# Relay_Board_V3.net
KiCad netlist of a schematic drawn in EAGLE
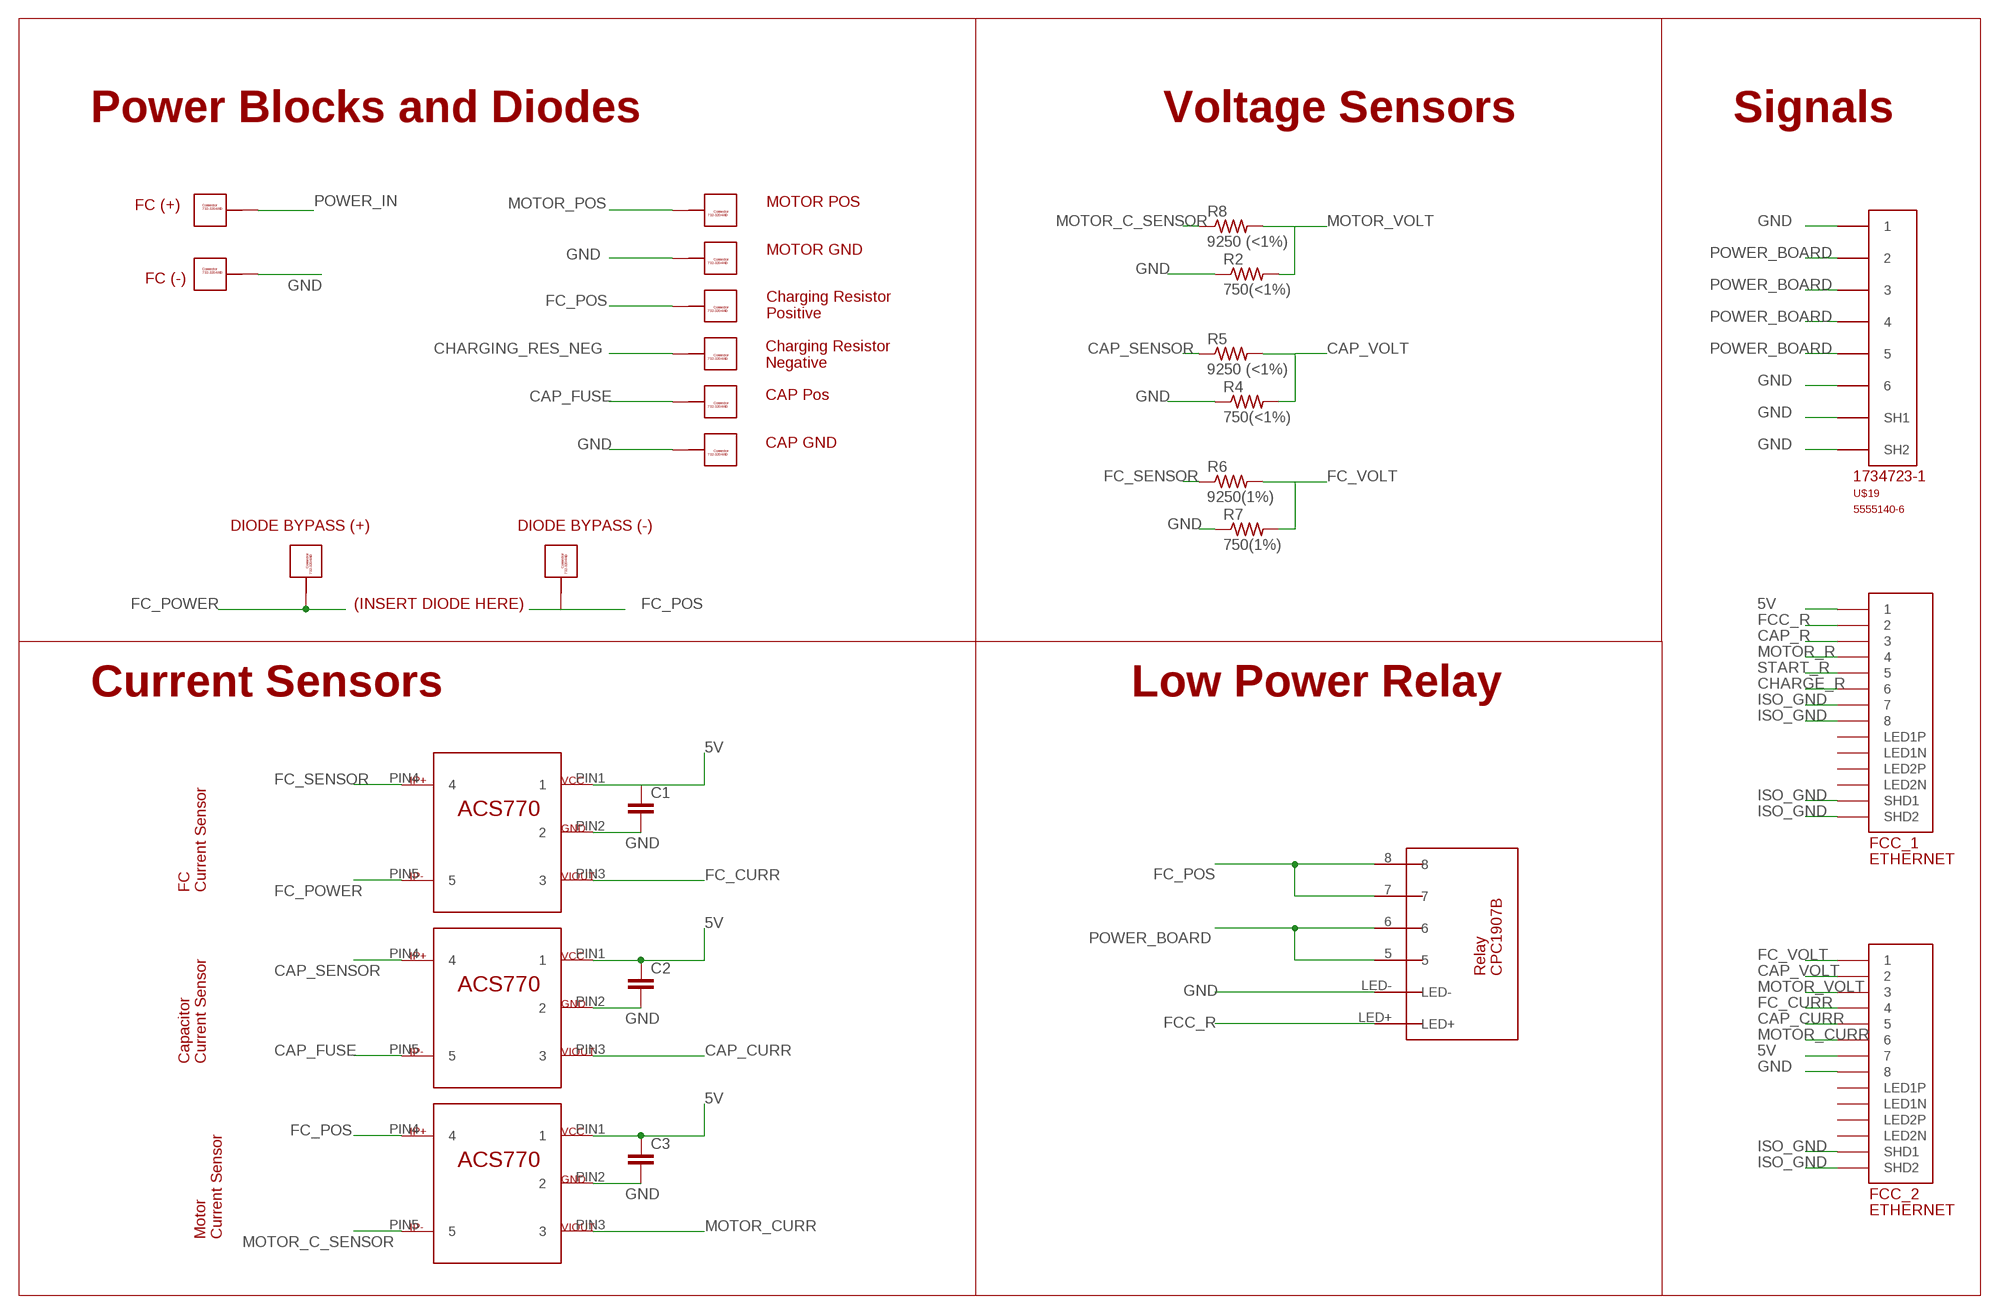
[diagram p0: schematic, sheet 1]
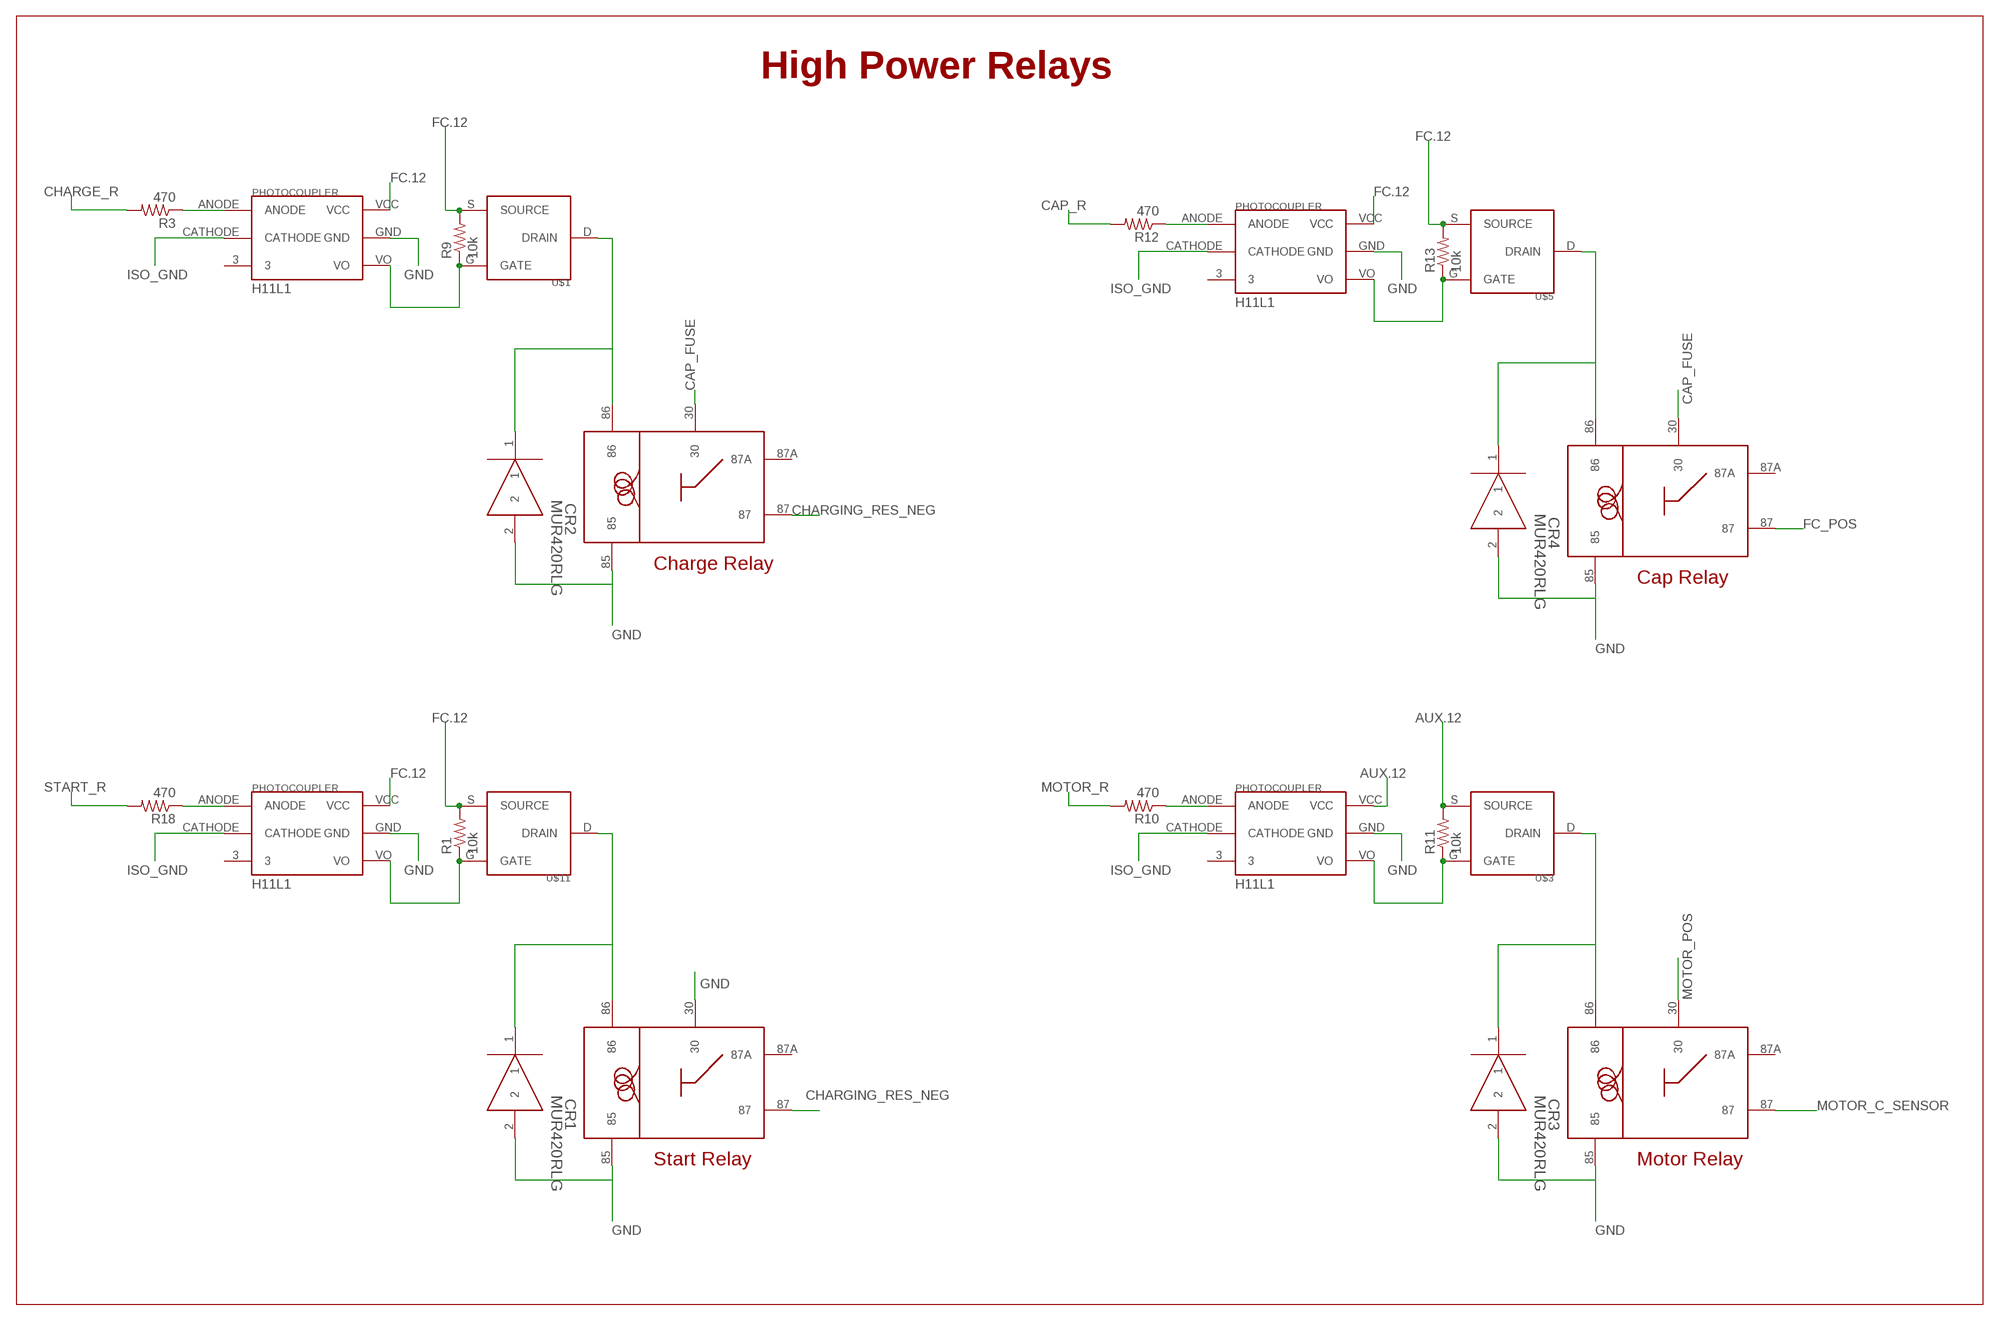
[diagram p1: schematic, sheet 2]

(export (version "E")
  (design (tool "Eeschema 10.0.6"))
  (components
    (comp (ref "C1")
      (value "CAP0603-CAP")
      (footprint "eagle-import:0603-CAP")
      (libsource (lib "eagle-import") (part "CAP0603-CAP"))
    )
    (comp (ref "C2")
      (value "CAP0603-CAP")
      (footprint "eagle-import:0603-CAP")
      (libsource (lib "eagle-import") (part "CAP0603-CAP"))
    )
    (comp (ref "C3")
      (value "CAP0603-CAP")
      (footprint "eagle-import:0603-CAP")
      (libsource (lib "eagle-import") (part "CAP0603-CAP"))
    )
    (comp (ref "CAP.GND")
      (value "732-3204-ND_CONNECTOR")
      (footprint "eagle-import:732-3204-ND")
      (libsource (lib "eagle-import") (part "732-3204-ND_CONNECTOR"))
    )
    (comp (ref "CAP.GND1")
      (value "732-3204-ND_CONNECTOR")
      (footprint "eagle-import:732-3204-ND")
      (libsource (lib "eagle-import") (part "732-3204-ND_CONNECTOR"))
    )
    (comp (ref "CAP.POS1")
      (value "732-3204-ND_CONNECTOR")
      (footprint "eagle-import:732-3204-ND")
      (libsource (lib "eagle-import") (part "732-3204-ND_CONNECTOR"))
    )
    (comp (ref "CAP.POS2")
      (value "732-3204-ND_CONNECTOR")
      (footprint "eagle-import:732-3204-ND")
      (libsource (lib "eagle-import") (part "732-3204-ND_CONNECTOR"))
    )
    (comp (ref "FC.GND")
      (value "732-3204-ND_CONNECTOR")
      (footprint "eagle-import:732-3204-ND")
      (libsource (lib "eagle-import") (part "732-3204-ND_CONNECTOR"))
    )
    (comp (ref "FC.POS")
      (value "732-3204-ND_CONNECTOR")
      (footprint "eagle-import:732-3204-ND")
      (libsource (lib "eagle-import") (part "732-3204-ND_CONNECTOR"))
    )
    (comp (ref "FCC_1")
      (value "ETHERNET")
      (footprint "eagle-import:A122645-ND")
      (libsource (lib "eagle-import") (part "ETHERNET"))
    )
    (comp (ref "FCC_2")
      (value "ETHERNET")
      (footprint "eagle-import:A122645-ND")
      (libsource (lib "eagle-import") (part "ETHERNET"))
    )
    (comp (ref "MOTOR.GROUND")
      (value "732-3204-ND_CONNECTOR")
      (footprint "eagle-import:732-3204-ND")
      (libsource (lib "eagle-import") (part "732-3204-ND_CONNECTOR"))
    )
    (comp (ref "MOTOR.POSITIVE")
      (value "732-3204-ND_CONNECTOR")
      (footprint "eagle-import:732-3204-ND")
      (libsource (lib "eagle-import") (part "732-3204-ND_CONNECTOR"))
    )
    (comp (ref "R2")
      (value "750(<1%)")
      (footprint "eagle-import:R0805")
      (libsource (lib "eagle-import") (part "R-US_R0805"))
    )
    (comp (ref "R4")
      (value "750(<1%)")
      (footprint "eagle-import:R0805")
      (libsource (lib "eagle-import") (part "R-US_R0805"))
    )
    (comp (ref "R5")
      (value "9250 (<1%)")
      (footprint "eagle-import:R0805")
      (libsource (lib "eagle-import") (part "R-US_R0805"))
    )
    (comp (ref "R6")
      (value "9250(1%)")
      (footprint "eagle-import:R0805")
      (libsource (lib "eagle-import") (part "R-US_R0805"))
    )
    (comp (ref "R7")
      (value "750(1%)")
      (footprint "eagle-import:R0805")
      (libsource (lib "eagle-import") (part "R-US_R0805"))
    )
    (comp (ref "R8")
      (value "9250 (<1%)")
      (footprint "eagle-import:R0805")
      (libsource (lib "eagle-import") (part "R-US_R0805"))
    )
    (comp (ref "RES.NEG")
      (value "732-3204-ND_CONNECTOR")
      (footprint "eagle-import:732-3204-ND")
      (libsource (lib "eagle-import") (part "732-3204-ND_CONNECTOR"))
    )
    (comp (ref "RES.POS")
      (value "732-3204-ND_CONNECTOR")
      (footprint "eagle-import:732-3204-ND")
      (libsource (lib "eagle-import") (part "732-3204-ND_CONNECTOR"))
    )
    (comp (ref "U$7")
      (value "ACS770LCB_CURRENTSENSOR")
      (footprint "eagle-import:ACS770LCB_CURRENTSENSOR")
      (libsource (lib "eagle-import") (part "ACS770LCB_CURRENTSENSOR"))
    )
    (comp (ref "U$8")
      (value "ACS770LCB_CURRENTSENSOR")
      (footprint "eagle-import:ACS770LCB_CURRENTSENSOR")
      (libsource (lib "eagle-import") (part "ACS770LCB_CURRENTSENSOR"))
    )
    (comp (ref "U$9")
      (value "ACS770LCB_CURRENTSENSOR")
      (footprint "eagle-import:ACS770LCB_CURRENTSENSOR")
      (libsource (lib "eagle-import") (part "ACS770LCB_CURRENTSENSOR"))
    )
    (comp (ref "U$19")
      (value "5555140-6")
      (footprint "eagle-import:1734723-1_RJ11")
      (libsource (lib "eagle-import") (part "5555140-6"))
    )
    (comp (ref "U$22")
      (value "RELAY-CPC1907B")
      (footprint "eagle-import:RELAY-CPC1907B")
      (libsource (lib "eagle-import") (part "RELAY-CPC1907B"))
    )
    (comp (ref "CR1")
      (value "MUR420RLG")
      (footprint "eagle-import:DO-201AD")
      (libsource (lib "eagle-import") (part "MUR420RLG"))
    )
    (comp (ref "CR2")
      (value "MUR420RLG")
      (footprint "eagle-import:DO-201AD")
      (libsource (lib "eagle-import") (part "MUR420RLG"))
    )
    (comp (ref "CR3")
      (value "MUR420RLG")
      (footprint "eagle-import:DO-201AD")
      (libsource (lib "eagle-import") (part "MUR420RLG"))
    )
    (comp (ref "CR4")
      (value "MUR420RLG")
      (footprint "eagle-import:DO-201AD")
      (libsource (lib "eagle-import") (part "MUR420RLG"))
    )
    (comp (ref "R1")
      (value "10k")
      (footprint "eagle-import:0603-RES")
      (libsource (lib "eagle-import") (part "RESISTOR0603-RES"))
    )
    (comp (ref "R3")
      (value "470")
      (footprint "eagle-import:0603-RES")
      (libsource (lib "eagle-import") (part "RESISTOR0603-RES"))
    )
    (comp (ref "R9")
      (value "10k")
      (footprint "eagle-import:0603-RES")
      (libsource (lib "eagle-import") (part "RESISTOR0603-RES"))
    )
    (comp (ref "R10")
      (value "470")
      (footprint "eagle-import:0603-RES")
      (libsource (lib "eagle-import") (part "RESISTOR0603-RES"))
    )
    (comp (ref "R11")
      (value "10k")
      (footprint "eagle-import:0603-RES")
      (libsource (lib "eagle-import") (part "RESISTOR0603-RES"))
    )
    (comp (ref "R12")
      (value "470")
      (footprint "eagle-import:0603-RES")
      (libsource (lib "eagle-import") (part "RESISTOR0603-RES"))
    )
    (comp (ref "R13")
      (value "10k")
      (footprint "eagle-import:0603-RES")
      (libsource (lib "eagle-import") (part "RESISTOR0603-RES"))
    )
    (comp (ref "R18")
      (value "470")
      (footprint "eagle-import:0603-RES")
      (libsource (lib "eagle-import") (part "RESISTOR0603-RES"))
    )
    (comp (ref "START.RELAY1")
      (value "VCF4-1000")
      (footprint "eagle-import:VCF4-1000")
      (libsource (lib "eagle-import") (part "VCF4-1000"))
    )
    (comp (ref "START.RELAY2")
      (value "VCF4-1000")
      (footprint "eagle-import:VCF4-1000")
      (libsource (lib "eagle-import") (part "VCF4-1000"))
    )
    (comp (ref "START.RELAY3")
      (value "VCF4-1000")
      (footprint "eagle-import:VCF4-1000")
      (libsource (lib "eagle-import") (part "VCF4-1000"))
    )
    (comp (ref "START.RELAY4")
      (value "VCF4-1000")
      (footprint "eagle-import:VCF4-1000")
      (libsource (lib "eagle-import") (part "VCF4-1000"))
    )
    (comp (ref "U$1")
      (value "DMP3056L-7DMP3056L-7")
      (footprint "eagle-import:DMP3056L-7")
      (libsource (lib "eagle-import") (part "DMP3056L-7DMP3056L-7"))
    )
    (comp (ref "U$2")
      (value "H11L1H11L1")
      (footprint "eagle-import:H11L1")
      (libsource (lib "eagle-import") (part "H11L1H11L1"))
    )
    (comp (ref "U$3")
      (value "DMP3056L-7DMP3056L-7")
      (footprint "eagle-import:DMP3056L-7")
      (libsource (lib "eagle-import") (part "DMP3056L-7DMP3056L-7"))
    )
    (comp (ref "U$4")
      (value "H11L1H11L1")
      (footprint "eagle-import:H11L1")
      (libsource (lib "eagle-import") (part "H11L1H11L1"))
    )
    (comp (ref "U$5")
      (value "DMP3056L-7DMP3056L-7")
      (footprint "eagle-import:DMP3056L-7")
      (libsource (lib "eagle-import") (part "DMP3056L-7DMP3056L-7"))
    )
    (comp (ref "U$6")
      (value "H11L1H11L1")
      (footprint "eagle-import:H11L1")
      (libsource (lib "eagle-import") (part "H11L1H11L1"))
    )
    (comp (ref "U$11")
      (value "DMP3056L-7DMP3056L-7")
      (footprint "eagle-import:DMP3056L-7")
      (libsource (lib "eagle-import") (part "DMP3056L-7DMP3056L-7"))
    )
    (comp (ref "U$12")
      (value "H11L1H11L1")
      (footprint "eagle-import:H11L1")
      (libsource (lib "eagle-import") (part "H11L1H11L1"))
    )
  )
  (nets
    (net (code "1") (name "5V") (class "Default")
      (node (ref "C1") (pin "1") (pinfunction "1_1") (pintype "passive"))
      (node (ref "C2") (pin "1") (pinfunction "1_1") (pintype "passive"))
      (node (ref "C3") (pin "1") (pinfunction "1_1") (pintype "passive"))
      (node (ref "FCC_1") (pin "P$1") (pinfunction "1_P$1") (pintype "bidirectional"))
      (node (ref "FCC_2") (pin "P$7") (pinfunction "7_P$7") (pintype "bidirectional"))
      (node (ref "U$7") (pin "PIN1") (pinfunction "1_PIN1") (pintype "bidirectional"))
      (node (ref "U$8") (pin "PIN1") (pinfunction "1_PIN1") (pintype "bidirectional"))
      (node (ref "U$9") (pin "PIN1") (pinfunction "1_PIN1") (pintype "bidirectional"))
    )
    (net (code "2") (name "AUX.12") (class "Default")
      (node (ref "R11") (pin "2") (pinfunction "2_2") (pintype "passive"))
      (node (ref "U$3") (pin "S") (pinfunction "SOURCE_S") (pintype "bidirectional"))
      (node (ref "U$4") (pin "VCC") (pinfunction "VCC_VCC") (pintype "bidirectional"))
    )
    (net (code "3") (name "CAP_CURR") (class "Default")
      (node (ref "FCC_2") (pin "P$5") (pinfunction "5_P$5") (pintype "bidirectional"))
      (node (ref "U$8") (pin "PIN3") (pinfunction "3_PIN3") (pintype "bidirectional"))
    )
    (net (code "4") (name "CAP_FUSE") (class "Default")
      (node (ref "CAP.GND1") (pin "P$1") (pinfunction "P$1_P$1") (pintype "bidirectional"))
      (node (ref "CAP.GND1") (pin "P$10") (pinfunction "P$1_P$10") (pintype "bidirectional"))
      (node (ref "CAP.GND1") (pin "P$2") (pinfunction "P$1_P$2") (pintype "bidirectional"))
      (node (ref "CAP.GND1") (pin "P$3") (pinfunction "P$1_P$3") (pintype "bidirectional"))
      (node (ref "CAP.GND1") (pin "P$4") (pinfunction "P$1_P$4") (pintype "bidirectional"))
      (node (ref "CAP.GND1") (pin "P$5") (pinfunction "P$1_P$5") (pintype "bidirectional"))
      (node (ref "CAP.GND1") (pin "P$6") (pinfunction "P$1_P$6") (pintype "bidirectional"))
      (node (ref "CAP.GND1") (pin "P$7") (pinfunction "P$1_P$7") (pintype "bidirectional"))
      (node (ref "CAP.GND1") (pin "P$8") (pinfunction "P$1_P$8") (pintype "bidirectional"))
      (node (ref "CAP.GND1") (pin "P$9") (pinfunction "P$1_P$9") (pintype "bidirectional"))
      (node (ref "START.RELAY2") (pin "30") (pinfunction "30_30") (pintype "bidirectional"))
      (node (ref "START.RELAY4") (pin "30") (pinfunction "30_30") (pintype "bidirectional"))
      (node (ref "U$8") (pin "PIN5") (pinfunction "5_PIN5") (pintype "bidirectional"))
    )
    (net (code "5") (name "CAP_R") (class "Default")
      (node (ref "FCC_1") (pin "P$3") (pinfunction "3_P$3") (pintype "bidirectional"))
      (node (ref "R12") (pin "2") (pinfunction "2_2") (pintype "passive"))
    )
    (net (code "6") (name "CAP_SENSOR") (class "Default")
      (node (ref "R5") (pin "1") (pinfunction "1_1") (pintype "passive"))
      (node (ref "U$8") (pin "PIN4") (pinfunction "4_PIN4") (pintype "bidirectional"))
    )
    (net (code "7") (name "CAP_VOLT") (class "Default")
      (node (ref "FCC_2") (pin "P$2") (pinfunction "2_P$2") (pintype "bidirectional"))
      (node (ref "R4") (pin "2") (pinfunction "2_2") (pintype "passive"))
      (node (ref "R5") (pin "2") (pinfunction "2_2") (pintype "passive"))
    )
    (net (code "8") (name "CHARGE_R") (class "Default")
      (node (ref "FCC_1") (pin "P$6") (pinfunction "6_P$6") (pintype "bidirectional"))
      (node (ref "R3") (pin "2") (pinfunction "2_2") (pintype "passive"))
    )
    (net (code "9") (name "CHARGING_RES_NEG") (class "Default")
      (node (ref "RES.NEG") (pin "P$1") (pinfunction "P$1_P$1") (pintype "bidirectional"))
      (node (ref "RES.NEG") (pin "P$10") (pinfunction "P$1_P$10") (pintype "bidirectional"))
      (node (ref "RES.NEG") (pin "P$2") (pinfunction "P$1_P$2") (pintype "bidirectional"))
      (node (ref "RES.NEG") (pin "P$3") (pinfunction "P$1_P$3") (pintype "bidirectional"))
      (node (ref "RES.NEG") (pin "P$4") (pinfunction "P$1_P$4") (pintype "bidirectional"))
      (node (ref "RES.NEG") (pin "P$5") (pinfunction "P$1_P$5") (pintype "bidirectional"))
      (node (ref "RES.NEG") (pin "P$6") (pinfunction "P$1_P$6") (pintype "bidirectional"))
      (node (ref "RES.NEG") (pin "P$7") (pinfunction "P$1_P$7") (pintype "bidirectional"))
      (node (ref "RES.NEG") (pin "P$8") (pinfunction "P$1_P$8") (pintype "bidirectional"))
      (node (ref "RES.NEG") (pin "P$9") (pinfunction "P$1_P$9") (pintype "bidirectional"))
      (node (ref "START.RELAY1") (pin "87") (pinfunction "87_87") (pintype "bidirectional"))
      (node (ref "START.RELAY2") (pin "87") (pinfunction "87_87") (pintype "bidirectional"))
    )
    (net (code "10") (name "FC.12") (class "Default")
      (node (ref "R1") (pin "2") (pinfunction "2_2") (pintype "passive"))
      (node (ref "R13") (pin "2") (pinfunction "2_2") (pintype "passive"))
      (node (ref "R9") (pin "2") (pinfunction "2_2") (pintype "passive"))
      (node (ref "U$1") (pin "S") (pinfunction "SOURCE_S") (pintype "bidirectional"))
      (node (ref "U$11") (pin "S") (pinfunction "SOURCE_S") (pintype "bidirectional"))
      (node (ref "U$12") (pin "VCC") (pinfunction "VCC_VCC") (pintype "bidirectional"))
      (node (ref "U$2") (pin "VCC") (pinfunction "VCC_VCC") (pintype "bidirectional"))
      (node (ref "U$5") (pin "S") (pinfunction "SOURCE_S") (pintype "bidirectional"))
      (node (ref "U$6") (pin "VCC") (pinfunction "VCC_VCC") (pintype "bidirectional"))
    )
    (net (code "11") (name "FCC_R") (class "Default")
      (node (ref "FCC_1") (pin "P$2") (pinfunction "2_P$2") (pintype "bidirectional"))
      (node (ref "U$22") (pin "LED+") (pinfunction "LED+_LED+") (pintype "bidirectional"))
    )
    (net (code "12") (name "FC_CURR") (class "Default")
      (node (ref "FCC_2") (pin "P$4") (pinfunction "4_P$4") (pintype "bidirectional"))
      (node (ref "U$7") (pin "PIN3") (pinfunction "3_PIN3") (pintype "bidirectional"))
    )
    (net (code "13") (name "FC_POS") (class "Default")
      (node (ref "CAP.POS2") (pin "P$1") (pinfunction "P$1_P$1") (pintype "bidirectional"))
      (node (ref "CAP.POS2") (pin "P$10") (pinfunction "P$1_P$10") (pintype "bidirectional"))
      (node (ref "CAP.POS2") (pin "P$2") (pinfunction "P$1_P$2") (pintype "bidirectional"))
      (node (ref "CAP.POS2") (pin "P$3") (pinfunction "P$1_P$3") (pintype "bidirectional"))
      (node (ref "CAP.POS2") (pin "P$4") (pinfunction "P$1_P$4") (pintype "bidirectional"))
      (node (ref "CAP.POS2") (pin "P$5") (pinfunction "P$1_P$5") (pintype "bidirectional"))
      (node (ref "CAP.POS2") (pin "P$6") (pinfunction "P$1_P$6") (pintype "bidirectional"))
      (node (ref "CAP.POS2") (pin "P$7") (pinfunction "P$1_P$7") (pintype "bidirectional"))
      (node (ref "CAP.POS2") (pin "P$8") (pinfunction "P$1_P$8") (pintype "bidirectional"))
      (node (ref "CAP.POS2") (pin "P$9") (pinfunction "P$1_P$9") (pintype "bidirectional"))
      (node (ref "RES.POS") (pin "P$1") (pinfunction "P$1_P$1") (pintype "bidirectional"))
      (node (ref "RES.POS") (pin "P$10") (pinfunction "P$1_P$10") (pintype "bidirectional"))
      (node (ref "RES.POS") (pin "P$2") (pinfunction "P$1_P$2") (pintype "bidirectional"))
      (node (ref "RES.POS") (pin "P$3") (pinfunction "P$1_P$3") (pintype "bidirectional"))
      (node (ref "RES.POS") (pin "P$4") (pinfunction "P$1_P$4") (pintype "bidirectional"))
      (node (ref "RES.POS") (pin "P$5") (pinfunction "P$1_P$5") (pintype "bidirectional"))
      (node (ref "RES.POS") (pin "P$6") (pinfunction "P$1_P$6") (pintype "bidirectional"))
      (node (ref "RES.POS") (pin "P$7") (pinfunction "P$1_P$7") (pintype "bidirectional"))
      (node (ref "RES.POS") (pin "P$8") (pinfunction "P$1_P$8") (pintype "bidirectional"))
      (node (ref "RES.POS") (pin "P$9") (pinfunction "P$1_P$9") (pintype "bidirectional"))
      (node (ref "START.RELAY4") (pin "87") (pinfunction "87_87") (pintype "bidirectional"))
      (node (ref "U$22") (pin "7") (pinfunction "7_7") (pintype "bidirectional"))
      (node (ref "U$22") (pin "8") (pinfunction "8_8") (pintype "bidirectional"))
      (node (ref "U$9") (pin "PIN4") (pinfunction "4_PIN4") (pintype "bidirectional"))
    )
    (net (code "14") (name "FC_POWER") (class "Default")
      (node (ref "CAP.POS1") (pin "P$1") (pinfunction "P$1_P$1") (pintype "bidirectional"))
      (node (ref "CAP.POS1") (pin "P$10") (pinfunction "P$1_P$10") (pintype "bidirectional"))
      (node (ref "CAP.POS1") (pin "P$2") (pinfunction "P$1_P$2") (pintype "bidirectional"))
      (node (ref "CAP.POS1") (pin "P$3") (pinfunction "P$1_P$3") (pintype "bidirectional"))
      (node (ref "CAP.POS1") (pin "P$4") (pinfunction "P$1_P$4") (pintype "bidirectional"))
      (node (ref "CAP.POS1") (pin "P$5") (pinfunction "P$1_P$5") (pintype "bidirectional"))
      (node (ref "CAP.POS1") (pin "P$6") (pinfunction "P$1_P$6") (pintype "bidirectional"))
      (node (ref "CAP.POS1") (pin "P$7") (pinfunction "P$1_P$7") (pintype "bidirectional"))
      (node (ref "CAP.POS1") (pin "P$8") (pinfunction "P$1_P$8") (pintype "bidirectional"))
      (node (ref "CAP.POS1") (pin "P$9") (pinfunction "P$1_P$9") (pintype "bidirectional"))
      (node (ref "U$7") (pin "PIN5") (pinfunction "5_PIN5") (pintype "bidirectional"))
    )
    (net (code "15") (name "FC_SENSOR") (class "Default")
      (node (ref "R6") (pin "1") (pinfunction "1_1") (pintype "passive"))
      (node (ref "U$7") (pin "PIN4") (pinfunction "4_PIN4") (pintype "bidirectional"))
    )
    (net (code "16") (name "FC_VOLT") (class "Default")
      (node (ref "FCC_2") (pin "P$1") (pinfunction "1_P$1") (pintype "bidirectional"))
      (node (ref "R6") (pin "2") (pinfunction "2_2") (pintype "passive"))
      (node (ref "R7") (pin "2") (pinfunction "2_2") (pintype "passive"))
    )
    (net (code "17") (name "GND") (class "Default")
      (node (ref "C1") (pin "2") (pinfunction "2_2") (pintype "passive"))
      (node (ref "C2") (pin "2") (pinfunction "2_2") (pintype "passive"))
      (node (ref "C3") (pin "2") (pinfunction "2_2") (pintype "passive"))
      (node (ref "CAP.GND") (pin "P$1") (pinfunction "P$1_P$1") (pintype "bidirectional"))
      (node (ref "CAP.GND") (pin "P$10") (pinfunction "P$1_P$10") (pintype "bidirectional"))
      (node (ref "CAP.GND") (pin "P$2") (pinfunction "P$1_P$2") (pintype "bidirectional"))
      (node (ref "CAP.GND") (pin "P$3") (pinfunction "P$1_P$3") (pintype "bidirectional"))
      (node (ref "CAP.GND") (pin "P$4") (pinfunction "P$1_P$4") (pintype "bidirectional"))
      (node (ref "CAP.GND") (pin "P$5") (pinfunction "P$1_P$5") (pintype "bidirectional"))
      (node (ref "CAP.GND") (pin "P$6") (pinfunction "P$1_P$6") (pintype "bidirectional"))
      (node (ref "CAP.GND") (pin "P$7") (pinfunction "P$1_P$7") (pintype "bidirectional"))
      (node (ref "CAP.GND") (pin "P$8") (pinfunction "P$1_P$8") (pintype "bidirectional"))
      (node (ref "CAP.GND") (pin "P$9") (pinfunction "P$1_P$9") (pintype "bidirectional"))
      (node (ref "CR1") (pin "2") (pinfunction "2_2") (pintype "passive"))
      (node (ref "CR2") (pin "2") (pinfunction "2_2") (pintype "passive"))
      (node (ref "CR3") (pin "2") (pinfunction "2_2") (pintype "passive"))
      (node (ref "CR4") (pin "2") (pinfunction "2_2") (pintype "passive"))
      (node (ref "FC.GND") (pin "P$1") (pinfunction "P$1_P$1") (pintype "bidirectional"))
      (node (ref "FC.GND") (pin "P$10") (pinfunction "P$1_P$10") (pintype "bidirectional"))
      (node (ref "FC.GND") (pin "P$2") (pinfunction "P$1_P$2") (pintype "bidirectional"))
      (node (ref "FC.GND") (pin "P$3") (pinfunction "P$1_P$3") (pintype "bidirectional"))
      (node (ref "FC.GND") (pin "P$4") (pinfunction "P$1_P$4") (pintype "bidirectional"))
      (node (ref "FC.GND") (pin "P$5") (pinfunction "P$1_P$5") (pintype "bidirectional"))
      (node (ref "FC.GND") (pin "P$6") (pinfunction "P$1_P$6") (pintype "bidirectional"))
      (node (ref "FC.GND") (pin "P$7") (pinfunction "P$1_P$7") (pintype "bidirectional"))
      (node (ref "FC.GND") (pin "P$8") (pinfunction "P$1_P$8") (pintype "bidirectional"))
      (node (ref "FC.GND") (pin "P$9") (pinfunction "P$1_P$9") (pintype "bidirectional"))
      (node (ref "FCC_2") (pin "P$8") (pinfunction "8_P$8") (pintype "bidirectional"))
      (node (ref "MOTOR.GROUND") (pin "P$1") (pinfunction "P$1_P$1") (pintype "bidirectional"))
      (node (ref "MOTOR.GROUND") (pin "P$10") (pinfunction "P$1_P$10") (pintype "bidirectional"))
      (node (ref "MOTOR.GROUND") (pin "P$2") (pinfunction "P$1_P$2") (pintype "bidirectional"))
      (node (ref "MOTOR.GROUND") (pin "P$3") (pinfunction "P$1_P$3") (pintype "bidirectional"))
      (node (ref "MOTOR.GROUND") (pin "P$4") (pinfunction "P$1_P$4") (pintype "bidirectional"))
      (node (ref "MOTOR.GROUND") (pin "P$5") (pinfunction "P$1_P$5") (pintype "bidirectional"))
      (node (ref "MOTOR.GROUND") (pin "P$6") (pinfunction "P$1_P$6") (pintype "bidirectional"))
      (node (ref "MOTOR.GROUND") (pin "P$7") (pinfunction "P$1_P$7") (pintype "bidirectional"))
      (node (ref "MOTOR.GROUND") (pin "P$8") (pinfunction "P$1_P$8") (pintype "bidirectional"))
      (node (ref "MOTOR.GROUND") (pin "P$9") (pinfunction "P$1_P$9") (pintype "bidirectional"))
      (node (ref "R2") (pin "1") (pinfunction "1_1") (pintype "passive"))
      (node (ref "R4") (pin "1") (pinfunction "1_1") (pintype "passive"))
      (node (ref "R7") (pin "1") (pinfunction "1_1") (pintype "passive"))
      (node (ref "START.RELAY1") (pin "30") (pinfunction "30_30") (pintype "bidirectional"))
      (node (ref "START.RELAY1") (pin "85") (pinfunction "85_85") (pintype "bidirectional"))
      (node (ref "START.RELAY2") (pin "85") (pinfunction "85_85") (pintype "bidirectional"))
      (node (ref "START.RELAY3") (pin "85") (pinfunction "85_85") (pintype "bidirectional"))
      (node (ref "START.RELAY4") (pin "85") (pinfunction "85_85") (pintype "bidirectional"))
      (node (ref "U$12") (pin "GND") (pinfunction "GND_GND") (pintype "bidirectional"))
      (node (ref "U$19") (pin "1") (pinfunction "1_1") (pintype "bidirectional"))
      (node (ref "U$19") (pin "6") (pinfunction "6_6") (pintype "bidirectional"))
      (node (ref "U$19") (pin "SH1") (pinfunction "SH1_SH1") (pintype "bidirectional"))
      (node (ref "U$19") (pin "SH2") (pinfunction "SH2_SH2") (pintype "bidirectional"))
      (node (ref "U$2") (pin "GND") (pinfunction "GND_GND") (pintype "bidirectional"))
      (node (ref "U$22") (pin "LED-") (pinfunction "LED-_LED-") (pintype "bidirectional"))
      (node (ref "U$4") (pin "GND") (pinfunction "GND_GND") (pintype "bidirectional"))
      (node (ref "U$6") (pin "GND") (pinfunction "GND_GND") (pintype "bidirectional"))
      (node (ref "U$7") (pin "PIN2") (pinfunction "2_PIN2") (pintype "bidirectional"))
      (node (ref "U$8") (pin "PIN2") (pinfunction "2_PIN2") (pintype "bidirectional"))
      (node (ref "U$9") (pin "PIN2") (pinfunction "2_PIN2") (pintype "bidirectional"))
    )
    (net (code "18") (name "ISO_GND") (class "Default")
      (node (ref "FCC_1") (pin "P$13") (pinfunction "SHD1_P$13") (pintype "bidirectional"))
      (node (ref "FCC_1") (pin "P$14") (pinfunction "SHD2_P$14") (pintype "bidirectional"))
      (node (ref "FCC_1") (pin "P$7") (pinfunction "7_P$7") (pintype "bidirectional"))
      (node (ref "FCC_1") (pin "P$8") (pinfunction "8_P$8") (pintype "bidirectional"))
      (node (ref "FCC_2") (pin "P$13") (pinfunction "SHD1_P$13") (pintype "bidirectional"))
      (node (ref "FCC_2") (pin "P$14") (pinfunction "SHD2_P$14") (pintype "bidirectional"))
      (node (ref "U$12") (pin "CATHODE") (pinfunction "CATHODE_CATHODE") (pintype "bidirectional"))
      (node (ref "U$2") (pin "CATHODE") (pinfunction "CATHODE_CATHODE") (pintype "bidirectional"))
      (node (ref "U$4") (pin "CATHODE") (pinfunction "CATHODE_CATHODE") (pintype "bidirectional"))
      (node (ref "U$6") (pin "CATHODE") (pinfunction "CATHODE_CATHODE") (pintype "bidirectional"))
    )
    (net (code "19") (name "MOTOR_CURR") (class "Default")
      (node (ref "FCC_2") (pin "P$6") (pinfunction "6_P$6") (pintype "bidirectional"))
      (node (ref "U$9") (pin "PIN3") (pinfunction "3_PIN3") (pintype "bidirectional"))
    )
    (net (code "20") (name "MOTOR_C_SENSOR") (class "Default")
      (node (ref "R8") (pin "1") (pinfunction "1_1") (pintype "passive"))
      (node (ref "START.RELAY3") (pin "87") (pinfunction "87_87") (pintype "bidirectional"))
      (node (ref "U$9") (pin "PIN5") (pinfunction "5_PIN5") (pintype "bidirectional"))
    )
    (net (code "21") (name "MOTOR_POS") (class "Default")
      (node (ref "MOTOR.POSITIVE") (pin "P$1") (pinfunction "P$1_P$1") (pintype "bidirectional"))
      (node (ref "MOTOR.POSITIVE") (pin "P$10") (pinfunction "P$1_P$10") (pintype "bidirectional"))
      (node (ref "MOTOR.POSITIVE") (pin "P$2") (pinfunction "P$1_P$2") (pintype "bidirectional"))
      (node (ref "MOTOR.POSITIVE") (pin "P$3") (pinfunction "P$1_P$3") (pintype "bidirectional"))
      (node (ref "MOTOR.POSITIVE") (pin "P$4") (pinfunction "P$1_P$4") (pintype "bidirectional"))
      (node (ref "MOTOR.POSITIVE") (pin "P$5") (pinfunction "P$1_P$5") (pintype "bidirectional"))
      (node (ref "MOTOR.POSITIVE") (pin "P$6") (pinfunction "P$1_P$6") (pintype "bidirectional"))
      (node (ref "MOTOR.POSITIVE") (pin "P$7") (pinfunction "P$1_P$7") (pintype "bidirectional"))
      (node (ref "MOTOR.POSITIVE") (pin "P$8") (pinfunction "P$1_P$8") (pintype "bidirectional"))
      (node (ref "MOTOR.POSITIVE") (pin "P$9") (pinfunction "P$1_P$9") (pintype "bidirectional"))
      (node (ref "START.RELAY3") (pin "30") (pinfunction "30_30") (pintype "bidirectional"))
    )
    (net (code "22") (name "MOTOR_R") (class "Default")
      (node (ref "FCC_1") (pin "P$4") (pinfunction "4_P$4") (pintype "bidirectional"))
      (node (ref "R10") (pin "2") (pinfunction "2_2") (pintype "passive"))
    )
    (net (code "23") (name "MOTOR_VOLT") (class "Default")
      (node (ref "FCC_2") (pin "P$3") (pinfunction "3_P$3") (pintype "bidirectional"))
      (node (ref "R2") (pin "2") (pinfunction "2_2") (pintype "passive"))
      (node (ref "R8") (pin "2") (pinfunction "2_2") (pintype "passive"))
    )
    (net (code "24") (name "Net-(R3-Pad1)") (class "Default")
      (node (ref "R3") (pin "1") (pinfunction "1_1") (pintype "passive"))
      (node (ref "U$2") (pin "ANODE") (pinfunction "ANODE_ANODE") (pintype "bidirectional"))
    )
    (net (code "25") (name "Net-(R10-Pad1)") (class "Default")
      (node (ref "R10") (pin "1") (pinfunction "1_1") (pintype "passive"))
      (node (ref "U$4") (pin "ANODE") (pinfunction "ANODE_ANODE") (pintype "bidirectional"))
    )
    (net (code "26") (name "Net-(R12-Pad1)") (class "Default")
      (node (ref "R12") (pin "1") (pinfunction "1_1") (pintype "passive"))
      (node (ref "U$6") (pin "ANODE") (pinfunction "ANODE_ANODE") (pintype "bidirectional"))
    )
    (net (code "27") (name "Net-(R18-Pad1)") (class "Default")
      (node (ref "R18") (pin "1") (pinfunction "1_1") (pintype "passive"))
      (node (ref "U$12") (pin "ANODE") (pinfunction "ANODE_ANODE") (pintype "bidirectional"))
    )
    (net (code "28") (name "Net-(U$1-DRAIN)") (class "Default")
      (node (ref "CR2") (pin "1") (pinfunction "1_1") (pintype "passive"))
      (node (ref "START.RELAY2") (pin "86") (pinfunction "86_86") (pintype "bidirectional"))
      (node (ref "U$1") (pin "D") (pinfunction "DRAIN_D") (pintype "bidirectional"))
    )
    (net (code "29") (name "Net-(U$1-GATE)") (class "Default")
      (node (ref "R9") (pin "1") (pinfunction "1_1") (pintype "passive"))
      (node (ref "U$1") (pin "G") (pinfunction "GATE_G") (pintype "bidirectional"))
      (node (ref "U$2") (pin "VO") (pinfunction "VO_VO") (pintype "bidirectional"))
    )
    (net (code "30") (name "Net-(U$3-DRAIN)") (class "Default")
      (node (ref "CR3") (pin "1") (pinfunction "1_1") (pintype "passive"))
      (node (ref "START.RELAY3") (pin "86") (pinfunction "86_86") (pintype "bidirectional"))
      (node (ref "U$3") (pin "D") (pinfunction "DRAIN_D") (pintype "bidirectional"))
    )
    (net (code "31") (name "Net-(U$3-GATE)") (class "Default")
      (node (ref "R11") (pin "1") (pinfunction "1_1") (pintype "passive"))
      (node (ref "U$3") (pin "G") (pinfunction "GATE_G") (pintype "bidirectional"))
      (node (ref "U$4") (pin "VO") (pinfunction "VO_VO") (pintype "bidirectional"))
    )
    (net (code "32") (name "Net-(U$5-DRAIN)") (class "Default")
      (node (ref "CR4") (pin "1") (pinfunction "1_1") (pintype "passive"))
      (node (ref "START.RELAY4") (pin "86") (pinfunction "86_86") (pintype "bidirectional"))
      (node (ref "U$5") (pin "D") (pinfunction "DRAIN_D") (pintype "bidirectional"))
    )
    (net (code "33") (name "Net-(U$5-GATE)") (class "Default")
      (node (ref "R13") (pin "1") (pinfunction "1_1") (pintype "passive"))
      (node (ref "U$5") (pin "G") (pinfunction "GATE_G") (pintype "bidirectional"))
      (node (ref "U$6") (pin "VO") (pinfunction "VO_VO") (pintype "bidirectional"))
    )
    (net (code "34") (name "Net-(U$11-DRAIN)") (class "Default")
      (node (ref "CR1") (pin "1") (pinfunction "1_1") (pintype "passive"))
      (node (ref "START.RELAY1") (pin "86") (pinfunction "86_86") (pintype "bidirectional"))
      (node (ref "U$11") (pin "D") (pinfunction "DRAIN_D") (pintype "bidirectional"))
    )
    (net (code "35") (name "Net-(U$11-GATE)") (class "Default")
      (node (ref "R1") (pin "1") (pinfunction "1_1") (pintype "passive"))
      (node (ref "U$11") (pin "G") (pinfunction "GATE_G") (pintype "bidirectional"))
      (node (ref "U$12") (pin "VO") (pinfunction "VO_VO") (pintype "bidirectional"))
    )
    (net (code "36") (name "POWER_BOARD") (class "Default")
      (node (ref "U$19") (pin "2") (pinfunction "2_2") (pintype "bidirectional"))
      (node (ref "U$19") (pin "3") (pinfunction "3_3") (pintype "bidirectional"))
      (node (ref "U$19") (pin "4") (pinfunction "4_4") (pintype "bidirectional"))
      (node (ref "U$19") (pin "5") (pinfunction "5_5") (pintype "bidirectional"))
      (node (ref "U$22") (pin "5") (pinfunction "5_5") (pintype "bidirectional"))
      (node (ref "U$22") (pin "6") (pinfunction "6_6") (pintype "bidirectional"))
    )
    (net (code "37") (name "POWER_IN") (class "Default")
      (node (ref "FC.POS") (pin "P$1") (pinfunction "P$1_P$1") (pintype "bidirectional"))
      (node (ref "FC.POS") (pin "P$10") (pinfunction "P$1_P$10") (pintype "bidirectional"))
      (node (ref "FC.POS") (pin "P$2") (pinfunction "P$1_P$2") (pintype "bidirectional"))
      (node (ref "FC.POS") (pin "P$3") (pinfunction "P$1_P$3") (pintype "bidirectional"))
      (node (ref "FC.POS") (pin "P$4") (pinfunction "P$1_P$4") (pintype "bidirectional"))
      (node (ref "FC.POS") (pin "P$5") (pinfunction "P$1_P$5") (pintype "bidirectional"))
      (node (ref "FC.POS") (pin "P$6") (pinfunction "P$1_P$6") (pintype "bidirectional"))
      (node (ref "FC.POS") (pin "P$7") (pinfunction "P$1_P$7") (pintype "bidirectional"))
      (node (ref "FC.POS") (pin "P$8") (pinfunction "P$1_P$8") (pintype "bidirectional"))
      (node (ref "FC.POS") (pin "P$9") (pinfunction "P$1_P$9") (pintype "bidirectional"))
    )
    (net (code "38") (name "START_R") (class "Default")
      (node (ref "FCC_1") (pin "P$5") (pinfunction "5_P$5") (pintype "bidirectional"))
      (node (ref "R18") (pin "2") (pinfunction "2_2") (pintype "passive"))
    )
    (net (code "39") (name "unconnected-(FCC_1-LED1N-PadP$9)") (class "Default")
      (node (ref "FCC_1") (pin "P$9") (pinfunction "LED1N_P$9") (pintype "bidirectional"))
    )
    (net (code "40") (name "unconnected-(FCC_1-LED1P-PadP$10)") (class "Default")
      (node (ref "FCC_1") (pin "P$10") (pinfunction "LED1P_P$10") (pintype "bidirectional"))
    )
    (net (code "41") (name "unconnected-(FCC_1-LED2N-PadP$11)") (class "Default")
      (node (ref "FCC_1") (pin "P$11") (pinfunction "LED2N_P$11") (pintype "bidirectional"))
    )
    (net (code "42") (name "unconnected-(FCC_1-LED2P-PadP$12)") (class "Default")
      (node (ref "FCC_1") (pin "P$12") (pinfunction "LED2P_P$12") (pintype "bidirectional"))
    )
    (net (code "43") (name "unconnected-(FCC_2-LED1N-PadP$9)") (class "Default")
      (node (ref "FCC_2") (pin "P$9") (pinfunction "LED1N_P$9") (pintype "bidirectional"))
    )
    (net (code "44") (name "unconnected-(FCC_2-LED1P-PadP$10)") (class "Default")
      (node (ref "FCC_2") (pin "P$10") (pinfunction "LED1P_P$10") (pintype "bidirectional"))
    )
    (net (code "45") (name "unconnected-(FCC_2-LED2N-PadP$11)") (class "Default")
      (node (ref "FCC_2") (pin "P$11") (pinfunction "LED2N_P$11") (pintype "bidirectional"))
    )
    (net (code "46") (name "unconnected-(FCC_2-LED2P-PadP$12)") (class "Default")
      (node (ref "FCC_2") (pin "P$12") (pinfunction "LED2P_P$12") (pintype "bidirectional"))
    )
    (net (code "47") (name "unconnected-(START.RELAY1-Pad87A)") (class "Default")
      (node (ref "START.RELAY1") (pin "87A") (pinfunction "87A_87A") (pintype "bidirectional"))
    )
    (net (code "48") (name "unconnected-(START.RELAY2-Pad87A)") (class "Default")
      (node (ref "START.RELAY2") (pin "87A") (pinfunction "87A_87A") (pintype "bidirectional"))
    )
    (net (code "49") (name "unconnected-(START.RELAY3-Pad87A)") (class "Default")
      (node (ref "START.RELAY3") (pin "87A") (pinfunction "87A_87A") (pintype "bidirectional"))
    )
    (net (code "50") (name "unconnected-(START.RELAY4-Pad87A)") (class "Default")
      (node (ref "START.RELAY4") (pin "87A") (pinfunction "87A_87A") (pintype "bidirectional"))
    )
    (net (code "51") (name "unconnected-(U$2-Pad3)") (class "Default")
      (node (ref "U$2") (pin "3") (pinfunction "3_3") (pintype "bidirectional"))
    )
    (net (code "52") (name "unconnected-(U$4-Pad3)") (class "Default")
      (node (ref "U$4") (pin "3") (pinfunction "3_3") (pintype "bidirectional"))
    )
    (net (code "53") (name "unconnected-(U$6-Pad3)") (class "Default")
      (node (ref "U$6") (pin "3") (pinfunction "3_3") (pintype "bidirectional"))
    )
    (net (code "54") (name "unconnected-(U$12-Pad3)") (class "Default")
      (node (ref "U$12") (pin "3") (pinfunction "3_3") (pintype "bidirectional"))
    )
  )
)
